# Sheet1.net
KiCad netlist of a schematic drawn in Altium Designer
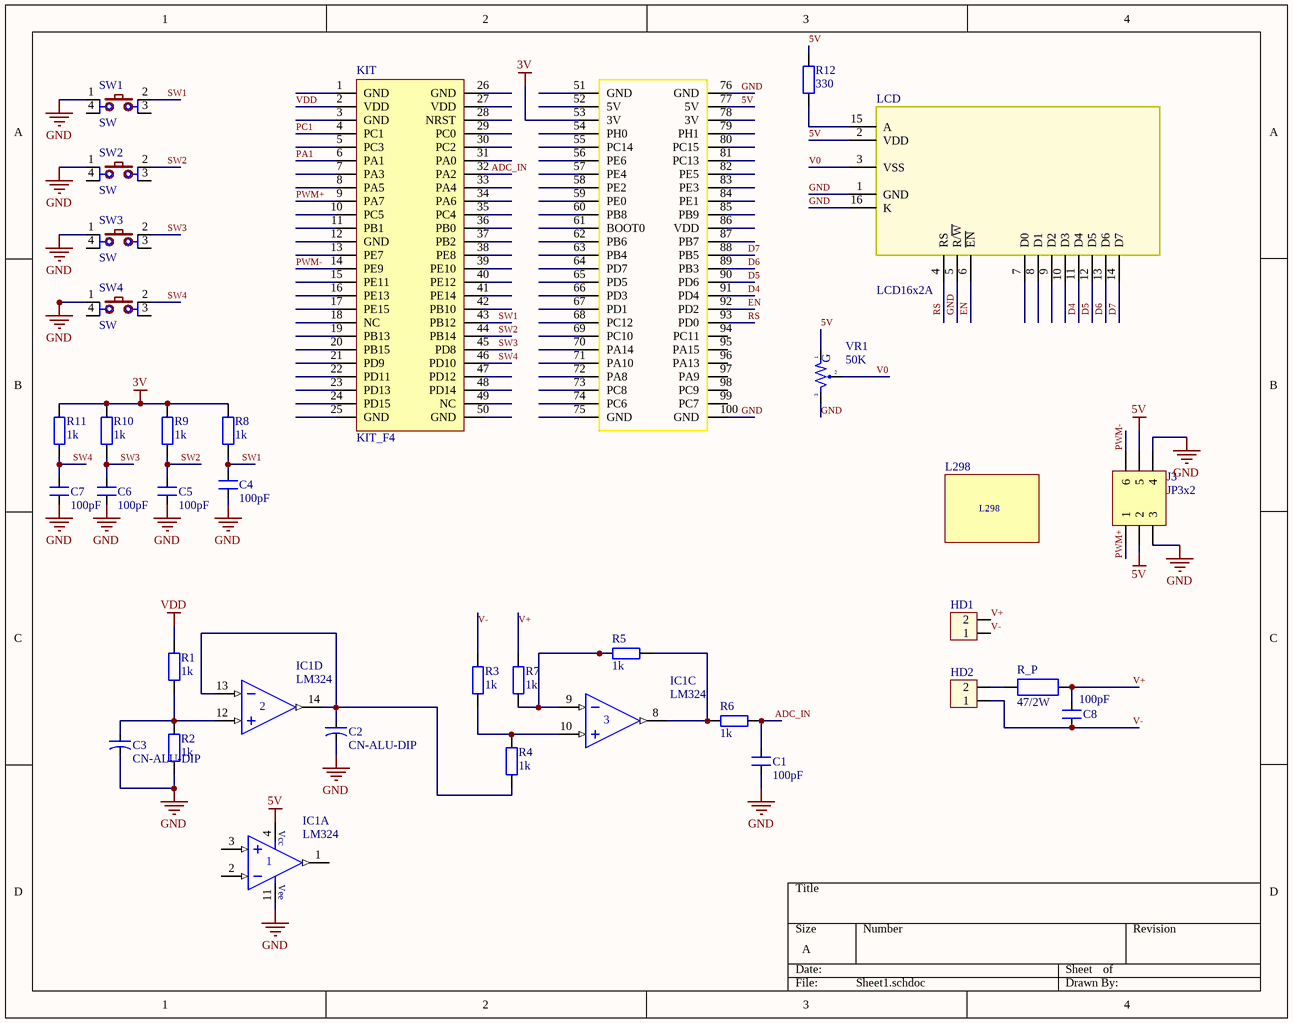
[diagram p0: Sheet1.schdoc]

(export (version "E")
  (design (tool "Eeschema 10.0.6"))
  (components
    (comp (ref "C1")
      (value "100pF")
      (footprint "CN1")
      (description "Cap np  1pF - 472pF")
      (libsource (lib "syhaunguyen") (part "CN1"))
    )
    (comp (ref "C2")
      (value "CN-ALU-DIP")
      (footprint "CA-ALU-2.54")
      (description "Capacitor (Semiconductor SIM Model)")
      (fields (field (name "PUBLISHER") "Altium Limited"))
      (libsource (lib "LIBRARY") (part "CN-ALU-DIP"))
    )
    (comp (ref "C3")
      (value "CN-ALU-DIP")
      (footprint "CA-ALU-2.54")
      (description "Capacitor (Semiconductor SIM Model)")
      (fields (field (name "PUBLISHER") "Altium Limited"))
      (libsource (lib "LIBRARY") (part "CN-ALU-DIP"))
    )
    (comp (ref "C4")
      (value "100pF")
      (footprint "CN1")
      (description "Cap np  1pF - 472pF")
      (libsource (lib "syhaunguyen") (part "CN1"))
    )
    (comp (ref "C5")
      (value "100pF")
      (footprint "CN1")
      (description "Cap np  1pF - 472pF")
      (libsource (lib "syhaunguyen") (part "CN1"))
    )
    (comp (ref "C6")
      (value "100pF")
      (footprint "CN1")
      (description "Cap np  1pF - 472pF")
      (libsource (lib "syhaunguyen") (part "CN1"))
    )
    (comp (ref "C7")
      (value "100pF")
      (footprint "CN1")
      (description "Cap np  1pF - 472pF")
      (libsource (lib "syhaunguyen") (part "CN1"))
    )
    (comp (ref "C8")
      (value "100pF")
      (footprint "CN1")
      (description "Cap np  1pF - 472pF")
      (libsource (lib "syhaunguyen") (part "CN1"))
    )
    (comp (ref "HD1")
      (value "Header 2")
      (footprint "HED2")
      (description "Header 2 (Green)")
      (libsource (lib "syhaunguyen") (part "Hed2"))
    )
    (comp (ref "HD2")
      (value "Header 2")
      (footprint "HED2")
      (description "Header 2 (Green)")
      (libsource (lib "syhaunguyen") (part "Hed2"))
    )
    (comp (ref "IC1")
      (value "LM324")
      (footprint "DIP14/W0.3")
      (description "Op x 4")
      (libsource (lib "syhaunguyen") (part "LM324"))
    )
    (comp (ref "J3")
      (value "JP3x2")
      (footprint "JP3-D2T")
      (description "WR-PHD 2.54 mm Dual Socket Header")
      (fields
        (field (name "MANUFACTURER") "Würth Elektronik eiSos GmbH")
        (field (name "PARTNO") "61300621821")
        (field (name "CREATED BY") "Karrer Zheng")
      )
      (libsource (lib "LIBRARY") (part "JP3x2"))
    )
    (comp (ref "KIT") (value "KIT_F4") (footprint "Kit-F4") (libsource (lib "Schlib1") (part "KIT_F4")))
    (comp (ref "L298") (value "L298") (footprint "L298") (libsource (lib "Schlib1") (part "L298")))
    (comp (ref "LCD")
      (value "LCD16x2A")
      (footprint "LCD16X2")
      (description "LCD dipslay 16 char, 2 line")
      (libsource (lib "syhaunguyen") (part "LCD16x2"))
    )
    (comp (ref "R1")
      (value "1k")
      (footprint "R1/4W")
      (description "Resistor 1/4W")
      (libsource (lib "syhaunguyen") (part "R1/4W"))
    )
    (comp (ref "R2")
      (value "1k")
      (footprint "R1/4W")
      (description "Resistor 1/4W")
      (libsource (lib "syhaunguyen") (part "R1/4W"))
    )
    (comp (ref "R3")
      (value "1k")
      (footprint "R1/4W")
      (description "Resistor 1/4W")
      (libsource (lib "syhaunguyen") (part "R1/4W"))
    )
    (comp (ref "R4")
      (value "1k")
      (footprint "R1/4W")
      (description "Resistor 1/4W")
      (libsource (lib "syhaunguyen") (part "R1/4W"))
    )
    (comp (ref "R5")
      (value "1k")
      (footprint "R1/4W")
      (description "Resistor 1/4W")
      (libsource (lib "syhaunguyen") (part "R1/4W"))
    )
    (comp (ref "R6")
      (value "1k")
      (footprint "R1/4W")
      (description "Resistor 1/4W")
      (libsource (lib "syhaunguyen") (part "R1/4W"))
    )
    (comp (ref "R7")
      (value "1k")
      (footprint "R1/4W")
      (description "Resistor 1/4W")
      (libsource (lib "syhaunguyen") (part "R1/4W"))
    )
    (comp (ref "R8")
      (value "1k")
      (footprint "R1/4W")
      (description "Resistor 1/4W")
      (libsource (lib "syhaunguyen") (part "R1/4W"))
    )
    (comp (ref "R9")
      (value "1k")
      (footprint "R1/4W")
      (description "Resistor 1/4W")
      (libsource (lib "syhaunguyen") (part "R1/4W"))
    )
    (comp (ref "R10")
      (value "1k")
      (footprint "R1/4W")
      (description "Resistor 1/4W")
      (libsource (lib "syhaunguyen") (part "R1/4W"))
    )
    (comp (ref "R11")
      (value "1k")
      (footprint "R1/4W")
      (description "Resistor 1/4W")
      (libsource (lib "syhaunguyen") (part "R1/4W"))
    )
    (comp (ref "R12")
      (value "330")
      (footprint "R1/4W")
      (description "Resistor 1/4W")
      (libsource (lib "syhaunguyen") (part "R1/4W"))
    )
    (comp (ref "R_P")
      (value "47/2W")
      (footprint "R2WD")
      (description "Resistor 2W")
      (libsource (lib "syhaunguyen") (part "R2W"))
    )
    (comp (ref "SW1")
      (value "SW")
      (footprint "SW2-DIP")
      (description "Switch button 4 pin")
      (libsource (lib "LIBRARY") (part "SW4"))
    )
    (comp (ref "SW2")
      (value "SW")
      (footprint "SW2-DIP")
      (description "Switch button 4 pin")
      (libsource (lib "LIBRARY") (part "SW4"))
    )
    (comp (ref "SW3")
      (value "SW")
      (footprint "SW2-DIP")
      (description "Switch button 4 pin")
      (libsource (lib "LIBRARY") (part "SW4"))
    )
    (comp (ref "SW4")
      (value "SW")
      (footprint "SW2-DIP")
      (description "Switch button 4 pin")
      (libsource (lib "LIBRARY") (part "SW4"))
    )
    (comp (ref "VR1")
      (value "50K")
      (footprint "VR-S2")
      (description "Var Resistor")
      (libsource (lib "LIBRARY") (part "VR-S"))
    )
  )
  (nets
    (net (code "1") (name "/ADC_IN") (class "Default")
      (node (ref "C1") (pin "2") (pinfunction "2_2") (pintype "passive"))
      (node (ref "KIT") (pin "32") (pinfunction "PA2_32") (pintype "passive"))
      (node (ref "R6") (pin "1") (pinfunction "1_1") (pintype "passive"))
    )
    (net (code "2") (name "/D4") (class "Default")
      (node (ref "KIT") (pin "91") (pinfunction "PD4_91") (pintype "passive"))
      (node (ref "LCD") (pin "11") (pinfunction "D4_11") (pintype "passive"))
    )
    (net (code "3") (name "/D5") (class "Default")
      (node (ref "KIT") (pin "90") (pinfunction "PD6_90") (pintype "passive"))
      (node (ref "LCD") (pin "12") (pinfunction "D5_12") (pintype "passive"))
    )
    (net (code "4") (name "/D6") (class "Default")
      (node (ref "KIT") (pin "89") (pinfunction "PB3_89") (pintype "passive"))
      (node (ref "LCD") (pin "13") (pinfunction "D6_13") (pintype "passive"))
    )
    (net (code "5") (name "/D7") (class "Default")
      (node (ref "KIT") (pin "88") (pinfunction "PB5_88") (pintype "passive"))
      (node (ref "LCD") (pin "14") (pinfunction "D7_14") (pintype "passive"))
    )
    (net (code "6") (name "/EN") (class "Default")
      (node (ref "KIT") (pin "92") (pinfunction "PD2_92") (pintype "passive"))
      (node (ref "LCD") (pin "6") (pinfunction "~{EN}_6") (pintype "passive"))
    )
    (net (code "7") (name "/PA1") (class "Default")
      (node (ref "KIT") (pin "6") (pinfunction "PA1_6") (pintype "passive"))
    )
    (net (code "8") (name "/PC1") (class "Default")
      (node (ref "KIT") (pin "4") (pinfunction "PC1_4") (pintype "passive"))
    )
    (net (code "9") (name "/PWM+") (class "Default")
      (node (ref "J3") (pin "1") (pinfunction "1_1") (pintype "passive"))
      (node (ref "KIT") (pin "9") (pinfunction "PA7_9") (pintype "passive"))
    )
    (net (code "10") (name "/PWM-") (class "Default")
      (node (ref "J3") (pin "6") (pinfunction "6_6") (pintype "passive"))
      (node (ref "KIT") (pin "14") (pinfunction "PE9_14") (pintype "passive"))
    )
    (net (code "11") (name "/RS") (class "Default")
      (node (ref "KIT") (pin "93") (pinfunction "PD0_93") (pintype "passive"))
      (node (ref "LCD") (pin "4") (pinfunction "RS_4") (pintype "passive"))
    )
    (net (code "12") (name "/SW1") (class "Default")
      (node (ref "C4") (pin "2") (pinfunction "2_2") (pintype "passive"))
      (node (ref "KIT") (pin "43") (pinfunction "PB12_43") (pintype "passive"))
      (node (ref "R8") (pin "1") (pinfunction "1_1") (pintype "passive"))
      (node (ref "SW1") (pin "2") (pinfunction "2_2") (pintype "passive"))
    )
    (net (code "13") (name "/SW2") (class "Default")
      (node (ref "C5") (pin "2") (pinfunction "2_2") (pintype "passive"))
      (node (ref "KIT") (pin "44") (pinfunction "PB14_44") (pintype "passive"))
      (node (ref "R9") (pin "1") (pinfunction "1_1") (pintype "passive"))
      (node (ref "SW2") (pin "2") (pinfunction "2_2") (pintype "passive"))
    )
    (net (code "14") (name "/SW3") (class "Default")
      (node (ref "C6") (pin "2") (pinfunction "2_2") (pintype "passive"))
      (node (ref "KIT") (pin "45") (pinfunction "PD8_45") (pintype "passive"))
      (node (ref "R10") (pin "1") (pinfunction "1_1") (pintype "passive"))
      (node (ref "SW3") (pin "2") (pinfunction "2_2") (pintype "passive"))
    )
    (net (code "15") (name "/SW4") (class "Default")
      (node (ref "C7") (pin "2") (pinfunction "2_2") (pintype "passive"))
      (node (ref "KIT") (pin "46") (pinfunction "PD10_46") (pintype "passive"))
      (node (ref "R11") (pin "1") (pinfunction "1_1") (pintype "passive"))
      (node (ref "SW4") (pin "2") (pinfunction "2_2") (pintype "passive"))
    )
    (net (code "16") (name "/V+") (class "Default")
      (node (ref "C8") (pin "2") (pinfunction "2_2") (pintype "passive"))
      (node (ref "HD1") (pin "2") (pinfunction "2_2") (pintype "passive"))
      (node (ref "R7") (pin "2") (pinfunction "2_2") (pintype "passive"))
      (node (ref "R_P") (pin "2") (pinfunction "2_2") (pintype "passive"))
    )
    (net (code "17") (name "/V-") (class "Default")
      (node (ref "C8") (pin "1") (pinfunction "1_1") (pintype "passive"))
      (node (ref "HD1") (pin "1") (pinfunction "1_1") (pintype "passive"))
      (node (ref "HD2") (pin "1") (pinfunction "1_1") (pintype "passive"))
      (node (ref "R3") (pin "2") (pinfunction "2_2") (pintype "passive"))
    )
    (net (code "18") (name "/V0") (class "Default")
      (node (ref "LCD") (pin "3") (pinfunction "VSS_3") (pintype "passive"))
      (node (ref "VR1") (pin "2") (pinfunction "2_2") (pintype "passive"))
    )
    (net (code "19") (name "3V") (class "Default")
      (node (ref "KIT") (pin "53") (pinfunction "3V_53") (pintype "passive"))
      (node (ref "R10") (pin "2") (pinfunction "2_2") (pintype "passive"))
      (node (ref "R11") (pin "2") (pinfunction "2_2") (pintype "passive"))
      (node (ref "R8") (pin "2") (pinfunction "2_2") (pintype "passive"))
      (node (ref "R9") (pin "2") (pinfunction "2_2") (pintype "passive"))
    )
    (net (code "20") (name "5V") (class "Default")
      (node (ref "IC1") (pin "4") (pinfunction "V+_4") (pintype "power_in"))
      (node (ref "J3") (pin "2") (pinfunction "2_2") (pintype "passive"))
      (node (ref "J3") (pin "5") (pinfunction "5_5") (pintype "passive"))
      (node (ref "KIT") (pin "77") (pinfunction "5V_77") (pintype "passive"))
      (node (ref "LCD") (pin "2") (pinfunction "VDD_2") (pintype "passive"))
      (node (ref "R12") (pin "2") (pinfunction "2_2") (pintype "passive"))
      (node (ref "VR1") (pin "1") (pinfunction "1_1") (pintype "passive"))
    )
    (net (code "21") (name "GND") (class "Default")
      (node (ref "C1") (pin "1") (pinfunction "1_1") (pintype "passive"))
      (node (ref "C2") (pin "2") (pinfunction "2_2") (pintype "passive"))
      (node (ref "C3") (pin "2") (pinfunction "2_2") (pintype "passive"))
      (node (ref "C4") (pin "1") (pinfunction "1_1") (pintype "passive"))
      (node (ref "C5") (pin "1") (pinfunction "1_1") (pintype "passive"))
      (node (ref "C6") (pin "1") (pinfunction "1_1") (pintype "passive"))
      (node (ref "C7") (pin "1") (pinfunction "1_1") (pintype "passive"))
      (node (ref "IC1") (pin "11") (pinfunction "V-_11") (pintype "power_in"))
      (node (ref "J3") (pin "3") (pinfunction "3_3") (pintype "passive"))
      (node (ref "J3") (pin "4") (pinfunction "4_4") (pintype "passive"))
      (node (ref "KIT") (pin "100") (pinfunction "GND_100") (pintype "passive"))
      (node (ref "KIT") (pin "76") (pinfunction "GND_76") (pintype "passive"))
      (node (ref "LCD") (pin "1") (pinfunction "GND_1") (pintype "passive"))
      (node (ref "LCD") (pin "16") (pinfunction "K_16") (pintype "passive"))
      (node (ref "LCD") (pin "5") (pinfunction "R/~{W}_5") (pintype "passive"))
      (node (ref "R2") (pin "1") (pinfunction "1_1") (pintype "passive"))
      (node (ref "SW1") (pin "1") (pintype "passive"))
      (node (ref "SW2") (pin "1") (pintype "passive"))
      (node (ref "SW3") (pin "1") (pintype "passive"))
      (node (ref "SW4") (pin "1") (pintype "passive"))
      (node (ref "VR1") (pin "3") (pinfunction "3_3") (pintype "passive"))
    )
    (net (code "22") (name "Net-(HD2-Pad2)") (class "Default")
      (node (ref "HD2") (pin "2") (pinfunction "2_2") (pintype "passive"))
      (node (ref "R_P") (pin "1") (pinfunction "1_1") (pintype "passive"))
    )
    (net (code "23") (name "Net-(IC1C-IN+)") (class "Default")
      (node (ref "IC1") (pin "10") (pinfunction "IN+_10") (pintype "input"))
      (node (ref "R3") (pin "1") (pinfunction "1_1") (pintype "passive"))
      (node (ref "R4") (pin "2") (pinfunction "2_2") (pintype "passive"))
    )
    (net (code "24") (name "Net-(IC1C-IN-)") (class "Default")
      (node (ref "IC1") (pin "9") (pinfunction "IN-_9") (pintype "input"))
      (node (ref "R5") (pin "2") (pinfunction "2_2") (pintype "passive"))
      (node (ref "R7") (pin "1") (pinfunction "1_1") (pintype "passive"))
    )
    (net (code "25") (name "Net-(IC1C-OUT)") (class "Default")
      (node (ref "IC1") (pin "8") (pinfunction "OUT_8") (pintype "output"))
      (node (ref "R5") (pin "1") (pinfunction "1_1") (pintype "passive"))
      (node (ref "R6") (pin "2") (pinfunction "2_2") (pintype "passive"))
    )
    (net (code "26") (name "Net-(IC1D-IN+)") (class "Default")
      (node (ref "C3") (pin "1") (pinfunction "1_1") (pintype "passive"))
      (node (ref "IC1") (pin "12") (pinfunction "IN+_12") (pintype "input"))
      (node (ref "R1") (pin "1") (pinfunction "1_1") (pintype "passive"))
      (node (ref "R2") (pin "2") (pinfunction "2_2") (pintype "passive"))
    )
    (net (code "27") (name "Net-(IC1D-IN-)") (class "Default")
      (node (ref "C2") (pin "1") (pinfunction "1_1") (pintype "passive"))
      (node (ref "IC1") (pin "13") (pinfunction "IN-_13") (pintype "input"))
      (node (ref "IC1") (pin "14") (pinfunction "OUT_14") (pintype "output"))
      (node (ref "R4") (pin "1") (pinfunction "1_1") (pintype "passive"))
    )
    (net (code "28") (name "Net-(LCD-A)") (class "Default")
      (node (ref "LCD") (pin "15") (pinfunction "A_15") (pintype "passive"))
      (node (ref "R12") (pin "1") (pinfunction "1_1") (pintype "passive"))
    )
    (net (code "29") (name "VDD") (class "Default")
      (node (ref "KIT") (pin "2") (pinfunction "VDD_2") (pintype "passive"))
      (node (ref "R1") (pin "2") (pinfunction "2_2") (pintype "passive"))
    )
    (net (code "30") (name "unconnected-(IC1A-IN+-Pad3)") (class "Default")
      (node (ref "IC1") (pin "3") (pinfunction "IN+_3") (pintype "input"))
    )
    (net (code "31") (name "unconnected-(IC1A-IN--Pad2)") (class "Default")
      (node (ref "IC1") (pin "2") (pinfunction "IN-_2") (pintype "input"))
    )
    (net (code "32") (name "unconnected-(IC1A-OUT-Pad1)") (class "Default")
      (node (ref "IC1") (pin "1") (pinfunction "OUT_1") (pintype "output"))
    )
    (net (code "33") (name "unconnected-(KIT-3V-Pad78)") (class "Default")
      (node (ref "KIT") (pin "78") (pinfunction "3V_78") (pintype "passive"))
    )
    (net (code "34") (name "unconnected-(KIT-5V-Pad52)") (class "Default")
      (node (ref "KIT") (pin "52") (pinfunction "5V_52") (pintype "passive"))
    )
    (net (code "35") (name "unconnected-(KIT-BOOT0-Pad61)") (class "Default")
      (node (ref "KIT") (pin "61") (pinfunction "BOOT0_61") (pintype "passive"))
    )
    (net (code "36") (name "unconnected-(KIT-GND-Pad1)") (class "Default")
      (node (ref "KIT") (pin "1") (pinfunction "GND_1") (pintype "passive"))
    )
    (net (code "37") (name "unconnected-(KIT-GND-Pad3)") (class "Default")
      (node (ref "KIT") (pin "3") (pinfunction "GND_3") (pintype "passive"))
    )
    (net (code "38") (name "unconnected-(KIT-GND-Pad12)") (class "Default")
      (node (ref "KIT") (pin "12") (pinfunction "GND_12") (pintype "passive"))
    )
    (net (code "39") (name "unconnected-(KIT-GND-Pad25)") (class "Default")
      (node (ref "KIT") (pin "25") (pinfunction "GND_25") (pintype "passive"))
    )
    (net (code "40") (name "unconnected-(KIT-GND-Pad26)") (class "Default")
      (node (ref "KIT") (pin "26") (pinfunction "GND_26") (pintype "passive"))
    )
    (net (code "41") (name "unconnected-(KIT-GND-Pad50)") (class "Default")
      (node (ref "KIT") (pin "50") (pinfunction "GND_50") (pintype "passive"))
    )
    (net (code "42") (name "unconnected-(KIT-GND-Pad51)") (class "Default")
      (node (ref "KIT") (pin "51") (pinfunction "GND_51") (pintype "passive"))
    )
    (net (code "43") (name "unconnected-(KIT-GND-Pad75)") (class "Default")
      (node (ref "KIT") (pin "75") (pinfunction "GND_75") (pintype "passive"))
    )
    (net (code "44") (name "unconnected-(KIT-NC-Pad18)") (class "Default")
      (node (ref "KIT") (pin "18") (pinfunction "NC_18") (pintype "passive"))
    )
    (net (code "45") (name "unconnected-(KIT-NC-Pad49)") (class "Default")
      (node (ref "KIT") (pin "49") (pinfunction "NC_49") (pintype "passive"))
    )
    (net (code "46") (name "unconnected-(KIT-NRST-Pad28)") (class "Default")
      (node (ref "KIT") (pin "28") (pinfunction "NRST_28") (pintype "passive"))
    )
    (net (code "47") (name "unconnected-(KIT-PA0-Pad31)") (class "Default")
      (node (ref "KIT") (pin "31") (pinfunction "PA0_31") (pintype "passive"))
    )
    (net (code "48") (name "unconnected-(KIT-PA3-Pad7)") (class "Default")
      (node (ref "KIT") (pin "7") (pinfunction "PA3_7") (pintype "passive"))
    )
    (net (code "49") (name "unconnected-(KIT-PA4-Pad33)") (class "Default")
      (node (ref "KIT") (pin "33") (pinfunction "PA4_33") (pintype "passive"))
    )
    (net (code "50") (name "unconnected-(KIT-PA5-Pad8)") (class "Default")
      (node (ref "KIT") (pin "8") (pinfunction "PA5_8") (pintype "passive"))
    )
    (net (code "51") (name "unconnected-(KIT-PA6-Pad34)") (class "Default")
      (node (ref "KIT") (pin "34") (pinfunction "PA6_34") (pintype "passive"))
    )
    (net (code "52") (name "unconnected-(KIT-PA8-Pad72)") (class "Default")
      (node (ref "KIT") (pin "72") (pinfunction "PA8_72") (pintype "passive"))
    )
    (net (code "53") (name "unconnected-(KIT-PA9-Pad97)") (class "Default")
      (node (ref "KIT") (pin "97") (pinfunction "PA9_97") (pintype "passive"))
    )
    (net (code "54") (name "unconnected-(KIT-PA10-Pad71)") (class "Default")
      (node (ref "KIT") (pin "71") (pinfunction "PA10_71") (pintype "passive"))
    )
    (net (code "55") (name "unconnected-(KIT-PA13-Pad96)") (class "Default")
      (node (ref "KIT") (pin "96") (pinfunction "PA13_96") (pintype "passive"))
    )
    (net (code "56") (name "unconnected-(KIT-PA14-Pad70)") (class "Default")
      (node (ref "KIT") (pin "70") (pinfunction "PA14_70") (pintype "passive"))
    )
    (net (code "57") (name "unconnected-(KIT-PA15-Pad95)") (class "Default")
      (node (ref "KIT") (pin "95") (pinfunction "PA15_95") (pintype "passive"))
    )
    (net (code "58") (name "unconnected-(KIT-PB0-Pad36)") (class "Default")
      (node (ref "KIT") (pin "36") (pinfunction "PB0_36") (pintype "passive"))
    )
    (net (code "59") (name "unconnected-(KIT-PB1-Pad11)") (class "Default")
      (node (ref "KIT") (pin "11") (pinfunction "PB1_11") (pintype "passive"))
    )
    (net (code "60") (name "unconnected-(KIT-PB2-Pad37)") (class "Default")
      (node (ref "KIT") (pin "37") (pinfunction "PB2_37") (pintype "passive"))
    )
    (net (code "61") (name "unconnected-(KIT-PB4-Pad63)") (class "Default")
      (node (ref "KIT") (pin "63") (pinfunction "PB4_63") (pintype "passive"))
    )
    (net (code "62") (name "unconnected-(KIT-PB6-Pad62)") (class "Default")
      (node (ref "KIT") (pin "62") (pinfunction "PB6_62") (pintype "passive"))
    )
    (net (code "63") (name "unconnected-(KIT-PB7-Pad87)") (class "Default")
      (node (ref "KIT") (pin "87") (pinfunction "PB7_87") (pintype "passive"))
    )
    (net (code "64") (name "unconnected-(KIT-PB8-Pad60)") (class "Default")
      (node (ref "KIT") (pin "60") (pinfunction "PB8_60") (pintype "passive"))
    )
    (net (code "65") (name "unconnected-(KIT-PB9-Pad85)") (class "Default")
      (node (ref "KIT") (pin "85") (pinfunction "PB9_85") (pintype "passive"))
    )
    (net (code "66") (name "unconnected-(KIT-PB10-Pad42)") (class "Default")
      (node (ref "KIT") (pin "42") (pinfunction "PB10_42") (pintype "passive"))
    )
    (net (code "67") (name "unconnected-(KIT-PB13-Pad19)") (class "Default")
      (node (ref "KIT") (pin "19") (pinfunction "PB13_19") (pintype "passive"))
    )
    (net (code "68") (name "unconnected-(KIT-PB15-Pad20)") (class "Default")
      (node (ref "KIT") (pin "20") (pinfunction "PB15_20") (pintype "passive"))
    )
    (net (code "69") (name "unconnected-(KIT-PC0-Pad29)") (class "Default")
      (node (ref "KIT") (pin "29") (pinfunction "PC0_29") (pintype "passive"))
    )
    (net (code "70") (name "unconnected-(KIT-PC2-Pad30)") (class "Default")
      (node (ref "KIT") (pin "30") (pinfunction "PC2_30") (pintype "passive"))
    )
    (net (code "71") (name "unconnected-(KIT-PC3-Pad5)") (class "Default")
      (node (ref "KIT") (pin "5") (pinfunction "PC3_5") (pintype "passive"))
    )
    (net (code "72") (name "unconnected-(KIT-PC4-Pad35)") (class "Default")
      (node (ref "KIT") (pin "35") (pinfunction "PC4_35") (pintype "passive"))
    )
    (net (code "73") (name "unconnected-(KIT-PC5-Pad10)") (class "Default")
      (node (ref "KIT") (pin "10") (pinfunction "PC5_10") (pintype "passive"))
    )
    (net (code "74") (name "unconnected-(KIT-PC6-Pad74)") (class "Default")
      (node (ref "KIT") (pin "74") (pinfunction "PC6_74") (pintype "passive"))
    )
    (net (code "75") (name "unconnected-(KIT-PC7-Pad99)") (class "Default")
      (node (ref "KIT") (pin "99") (pinfunction "PC7_99") (pintype "passive"))
    )
    (net (code "76") (name "unconnected-(KIT-PC8-Pad73)") (class "Default")
      (node (ref "KIT") (pin "73") (pinfunction "PC8_73") (pintype "passive"))
    )
    (net (code "77") (name "unconnected-(KIT-PC9-Pad98)") (class "Default")
      (node (ref "KIT") (pin "98") (pinfunction "PC9_98") (pintype "passive"))
    )
    (net (code "78") (name "unconnected-(KIT-PC10-Pad69)") (class "Default")
      (node (ref "KIT") (pin "69") (pinfunction "PC10_69") (pintype "passive"))
    )
    (net (code "79") (name "unconnected-(KIT-PC11-Pad94)") (class "Default")
      (node (ref "KIT") (pin "94") (pinfunction "PC11_94") (pintype "passive"))
    )
    (net (code "80") (name "unconnected-(KIT-PC12-Pad68)") (class "Default")
      (node (ref "KIT") (pin "68") (pinfunction "PC12_68") (pintype "passive"))
    )
    (net (code "81") (name "unconnected-(KIT-PC13-Pad81)") (class "Default")
      (node (ref "KIT") (pin "81") (pinfunction "PC13_81") (pintype "passive"))
    )
    (net (code "82") (name "unconnected-(KIT-PC14-Pad55)") (class "Default")
      (node (ref "KIT") (pin "55") (pinfunction "PC14_55") (pintype "passive"))
    )
    (net (code "83") (name "unconnected-(KIT-PC15-Pad80)") (class "Default")
      (node (ref "KIT") (pin "80") (pinfunction "PC15_80") (pintype "passive"))
    )
    (net (code "84") (name "unconnected-(KIT-PD1-Pad67)") (class "Default")
      (node (ref "KIT") (pin "67") (pinfunction "PD1_67") (pintype "passive"))
    )
    (net (code "85") (name "unconnected-(KIT-PD3-Pad66)") (class "Default")
      (node (ref "KIT") (pin "66") (pinfunction "PD3_66") (pintype "passive"))
    )
    (net (code "86") (name "unconnected-(KIT-PD5-Pad65)") (class "Default")
      (node (ref "KIT") (pin "65") (pinfunction "PD5_65") (pintype "passive"))
    )
    (net (code "87") (name "unconnected-(KIT-PD7-Pad64)") (class "Default")
      (node (ref "KIT") (pin "64") (pinfunction "PD7_64") (pintype "passive"))
    )
    (net (code "88") (name "unconnected-(KIT-PD9-Pad21)") (class "Default")
      (node (ref "KIT") (pin "21") (pinfunction "PD9_21") (pintype "passive"))
    )
    (net (code "89") (name "unconnected-(KIT-PD11-Pad22)") (class "Default")
      (node (ref "KIT") (pin "22") (pinfunction "PD11_22") (pintype "passive"))
    )
    (net (code "90") (name "unconnected-(KIT-PD12-Pad47)") (class "Default")
      (node (ref "KIT") (pin "47") (pinfunction "PD12_47") (pintype "passive"))
    )
    (net (code "91") (name "unconnected-(KIT-PD13-Pad23)") (class "Default")
      (node (ref "KIT") (pin "23") (pinfunction "PD13_23") (pintype "passive"))
    )
    (net (code "92") (name "unconnected-(KIT-PD14-Pad48)") (class "Default")
      (node (ref "KIT") (pin "48") (pinfunction "PD14_48") (pintype "passive"))
    )
    (net (code "93") (name "unconnected-(KIT-PD15-Pad24)") (class "Default")
      (node (ref "KIT") (pin "24") (pinfunction "PD15_24") (pintype "passive"))
    )
    (net (code "94") (name "unconnected-(KIT-PE0-Pad59)") (class "Default")
      (node (ref "KIT") (pin "59") (pinfunction "PE0_59") (pintype "passive"))
    )
    (net (code "95") (name "unconnected-(KIT-PE1-Pad84)") (class "Default")
      (node (ref "KIT") (pin "84") (pinfunction "PE1_84") (pintype "passive"))
    )
    (net (code "96") (name "unconnected-(KIT-PE2-Pad58)") (class "Default")
      (node (ref "KIT") (pin "58") (pinfunction "PE2_58") (pintype "passive"))
    )
    (net (code "97") (name "unconnected-(KIT-PE3-Pad83)") (class "Default")
      (node (ref "KIT") (pin "83") (pinfunction "PE3_83") (pintype "passive"))
    )
    (net (code "98") (name "unconnected-(KIT-PE4-Pad57)") (class "Default")
      (node (ref "KIT") (pin "57") (pinfunction "PE4_57") (pintype "passive"))
    )
    (net (code "99") (name "unconnected-(KIT-PE5-Pad82)") (class "Default")
      (node (ref "KIT") (pin "82") (pinfunction "PE5_82") (pintype "passive"))
    )
    (net (code "100") (name "unconnected-(KIT-PE6-Pad56)") (class "Default")
      (node (ref "KIT") (pin "56") (pinfunction "PE6_56") (pintype "passive"))
    )
    (net (code "101") (name "unconnected-(KIT-PE7-Pad13)") (class "Default")
      (node (ref "KIT") (pin "13") (pinfunction "PE7_13") (pintype "passive"))
    )
    (net (code "102") (name "unconnected-(KIT-PE8-Pad38)") (class "Default")
      (node (ref "KIT") (pin "38") (pinfunction "PE8_38") (pintype "passive"))
    )
    (net (code "103") (name "unconnected-(KIT-PE10-Pad39)") (class "Default")
      (node (ref "KIT") (pin "39") (pinfunction "PE10_39") (pintype "passive"))
    )
    (net (code "104") (name "unconnected-(KIT-PE11-Pad15)") (class "Default")
      (node (ref "KIT") (pin "15") (pinfunction "PE11_15") (pintype "passive"))
    )
    (net (code "105") (name "unconnected-(KIT-PE12-Pad40)") (class "Default")
      (node (ref "KIT") (pin "40") (pinfunction "PE12_40") (pintype "passive"))
    )
    (net (code "106") (name "unconnected-(KIT-PE13-Pad16)") (class "Default")
      (node (ref "KIT") (pin "16") (pinfunction "PE13_16") (pintype "passive"))
    )
    (net (code "107") (name "unconnected-(KIT-PE14-Pad41)") (class "Default")
      (node (ref "KIT") (pin "41") (pinfunction "PE14_41") (pintype "passive"))
    )
    (net (code "108") (name "unconnected-(KIT-PE15-Pad17)") (class "Default")
      (node (ref "KIT") (pin "17") (pinfunction "PE15_17") (pintype "passive"))
    )
    (net (code "109") (name "unconnected-(KIT-PH0-Pad54)") (class "Default")
      (node (ref "KIT") (pin "54") (pinfunction "PH0_54") (pintype "passive"))
    )
    (net (code "110") (name "unconnected-(KIT-PH1-Pad79)") (class "Default")
      (node (ref "KIT") (pin "79") (pinfunction "PH1_79") (pintype "passive"))
    )
    (net (code "111") (name "unconnected-(KIT-VDD-Pad27)") (class "Default")
      (node (ref "KIT") (pin "27") (pinfunction "VDD_27") (pintype "passive"))
    )
    (net (code "112") (name "unconnected-(KIT-VDD-Pad86)") (class "Default")
      (node (ref "KIT") (pin "86") (pinfunction "VDD_86") (pintype "passive"))
    )
    (net (code "113") (name "unconnected-(LCD-D0-Pad7)") (class "Default")
      (node (ref "LCD") (pin "7") (pinfunction "D0_7") (pintype "passive"))
    )
    (net (code "114") (name "unconnected-(LCD-D1-Pad8)") (class "Default")
      (node (ref "LCD") (pin "8") (pinfunction "D1_8") (pintype "passive"))
    )
    (net (code "115") (name "unconnected-(LCD-D2-Pad9)") (class "Default")
      (node (ref "LCD") (pin "9") (pinfunction "D2_9") (pintype "passive"))
    )
    (net (code "116") (name "unconnected-(LCD-D3-Pad10)") (class "Default")
      (node (ref "LCD") (pin "10") (pinfunction "D3_10") (pintype "passive"))
    )
    (net (code "117") (name "unconnected-(SW1-Pad3)") (class "Default")
      (node (ref "SW1") (pin "3") (pinfunction "3_3") (pintype "passive"))
    )
    (net (code "118") (name "unconnected-(SW1-Pad4)") (class "Default")
      (node (ref "SW1") (pin "4") (pinfunction "4_4") (pintype "passive"))
    )
    (net (code "119") (name "unconnected-(SW2-Pad3)") (class "Default")
      (node (ref "SW2") (pin "3") (pinfunction "3_3") (pintype "passive"))
    )
    (net (code "120") (name "unconnected-(SW2-Pad4)") (class "Default")
      (node (ref "SW2") (pin "4") (pinfunction "4_4") (pintype "passive"))
    )
    (net (code "121") (name "unconnected-(SW3-Pad3)") (class "Default")
      (node (ref "SW3") (pin "3") (pinfunction "3_3") (pintype "passive"))
    )
    (net (code "122") (name "unconnected-(SW3-Pad4)") (class "Default")
      (node (ref "SW3") (pin "4") (pinfunction "4_4") (pintype "passive"))
    )
    (net (code "123") (name "unconnected-(SW4-Pad3)") (class "Default")
      (node (ref "SW4") (pin "3") (pinfunction "3_3") (pintype "passive"))
    )
    (net (code "124") (name "unconnected-(SW4-Pad4)") (class "Default")
      (node (ref "SW4") (pin "4") (pinfunction "4_4") (pintype "passive"))
    )
  )
)
